# Hypnos_V0.net
KiCad netlist of a schematic drawn in EAGLE
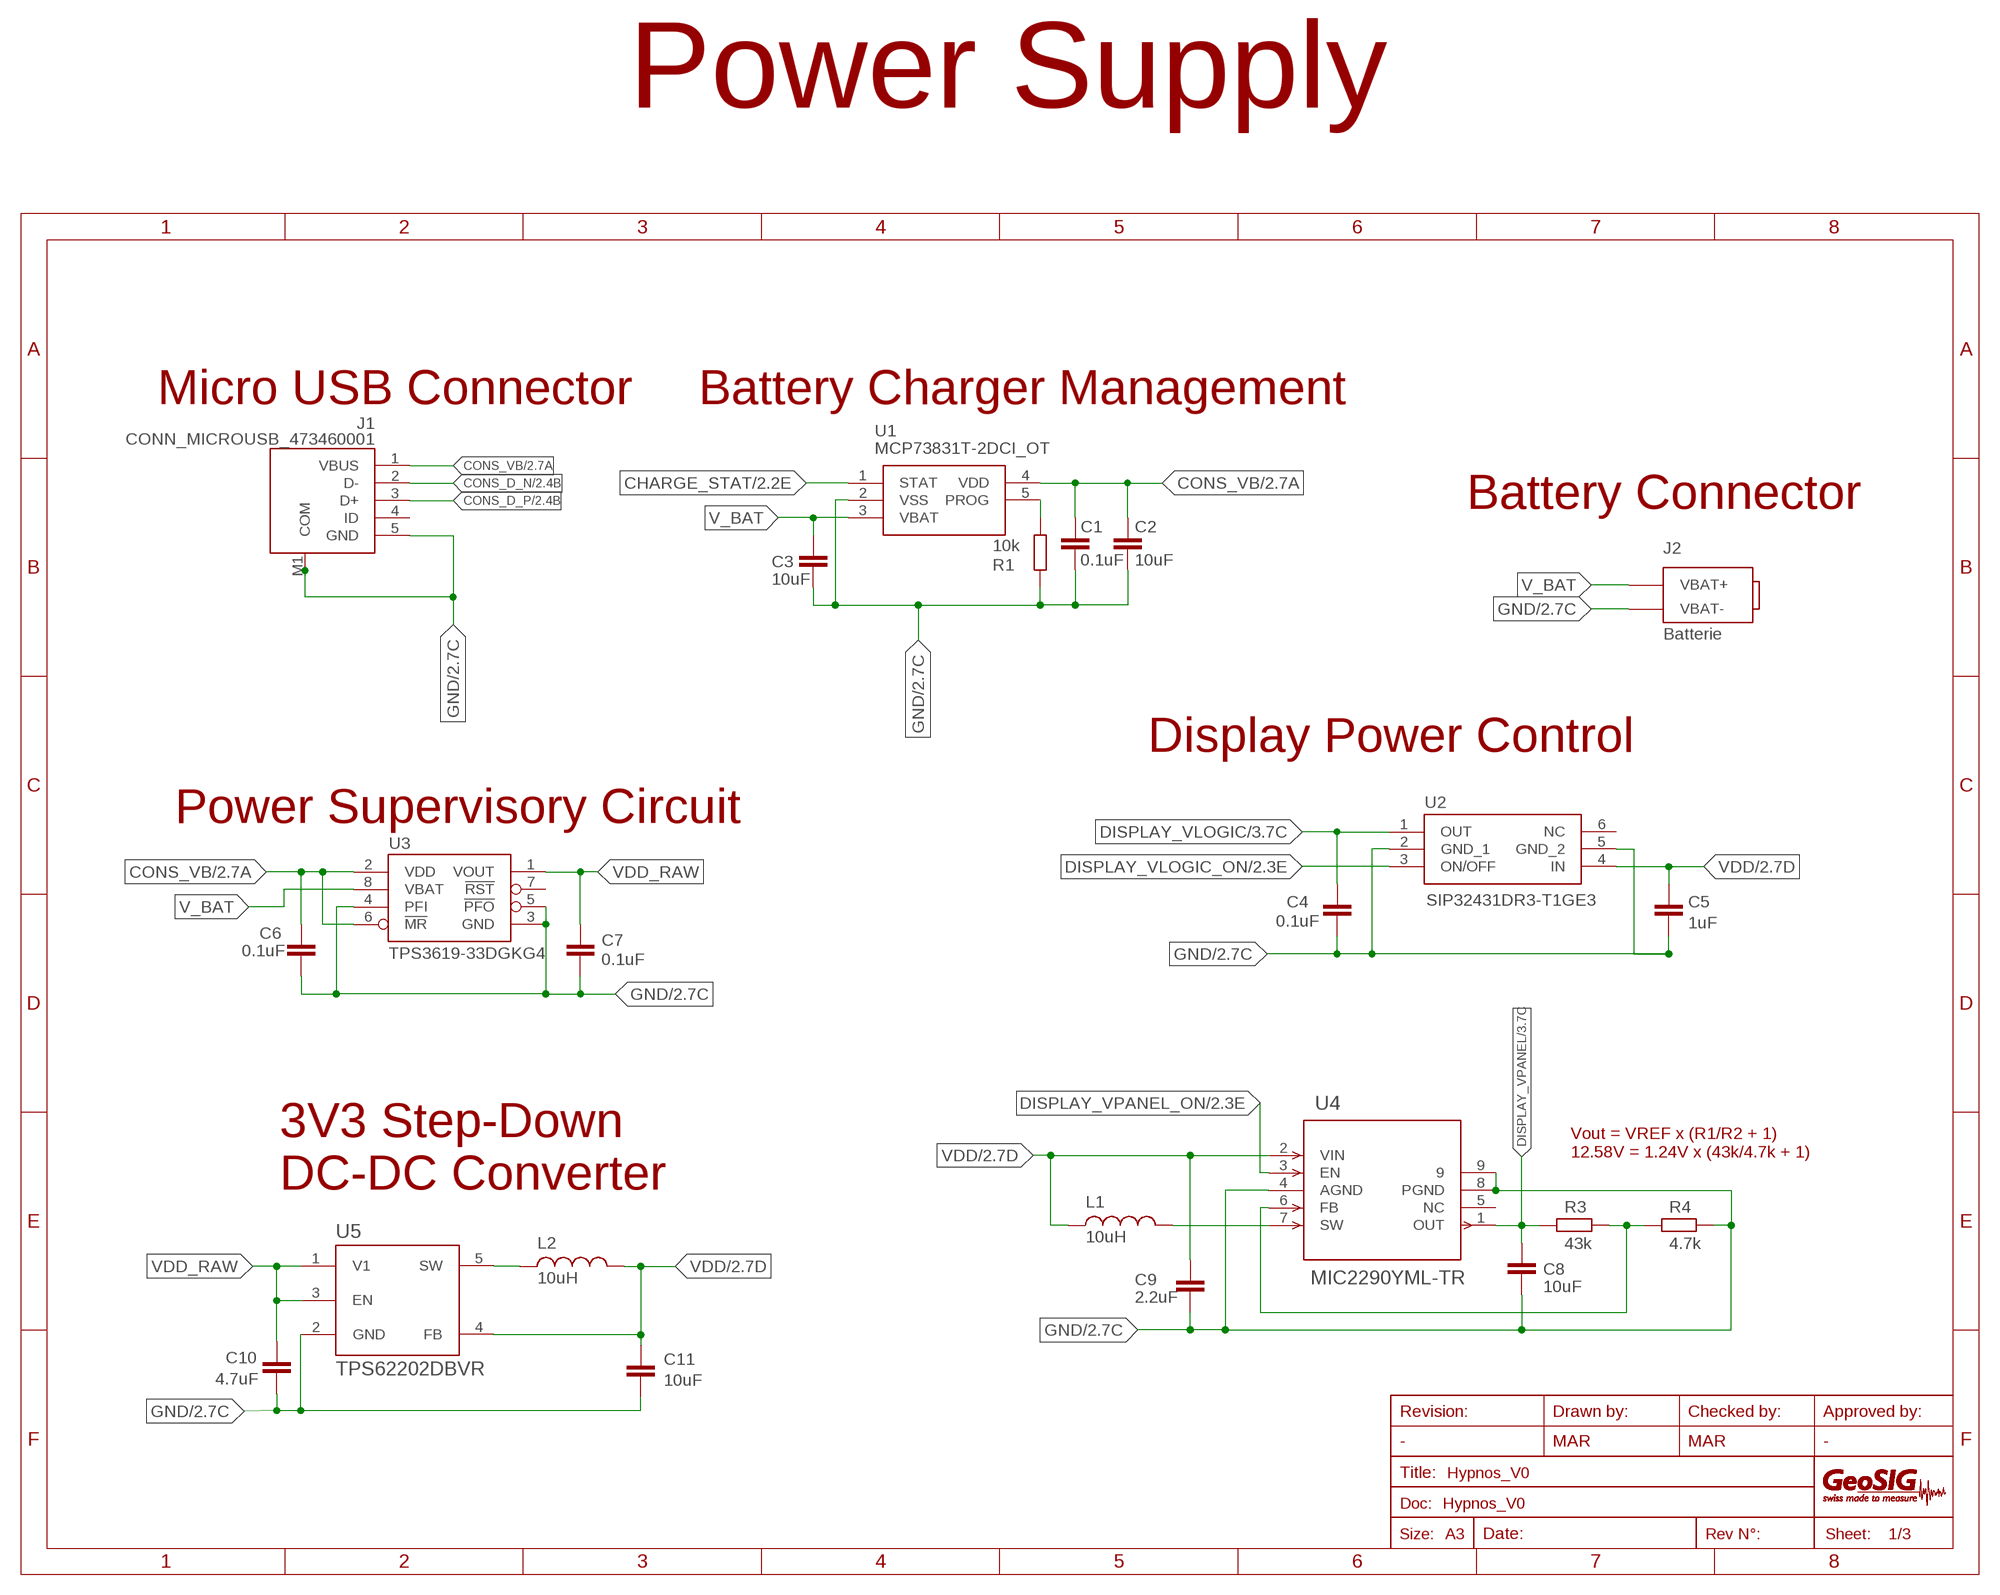
[diagram p0: schematic, sheet 1]
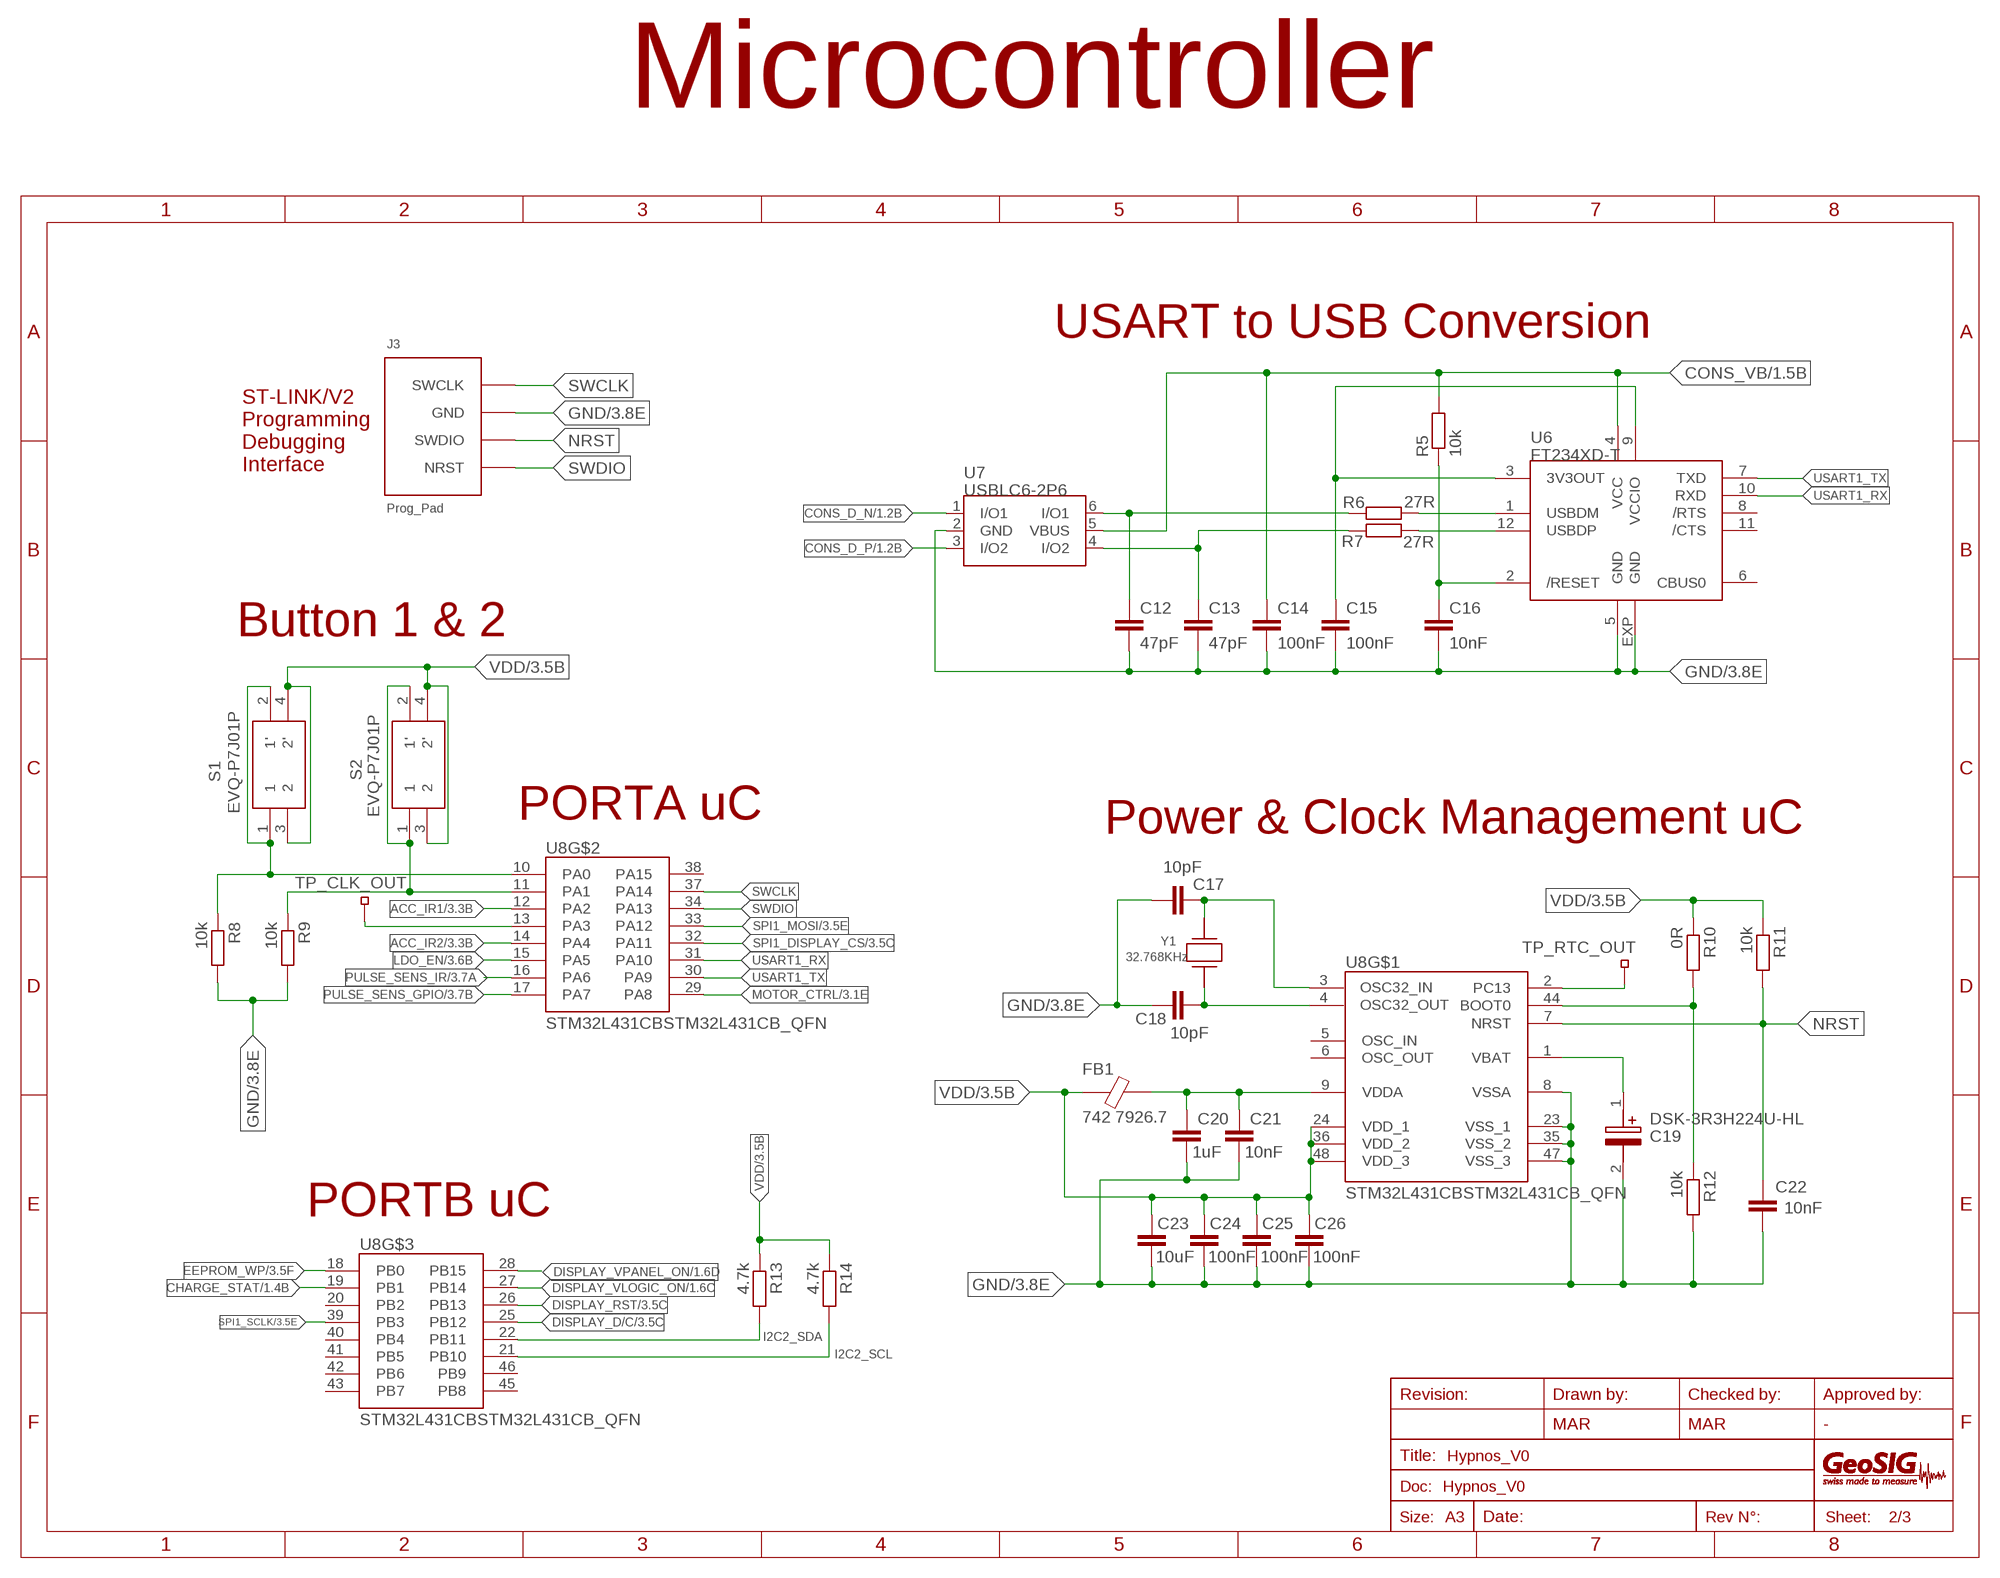
[diagram p1: schematic, sheet 2]
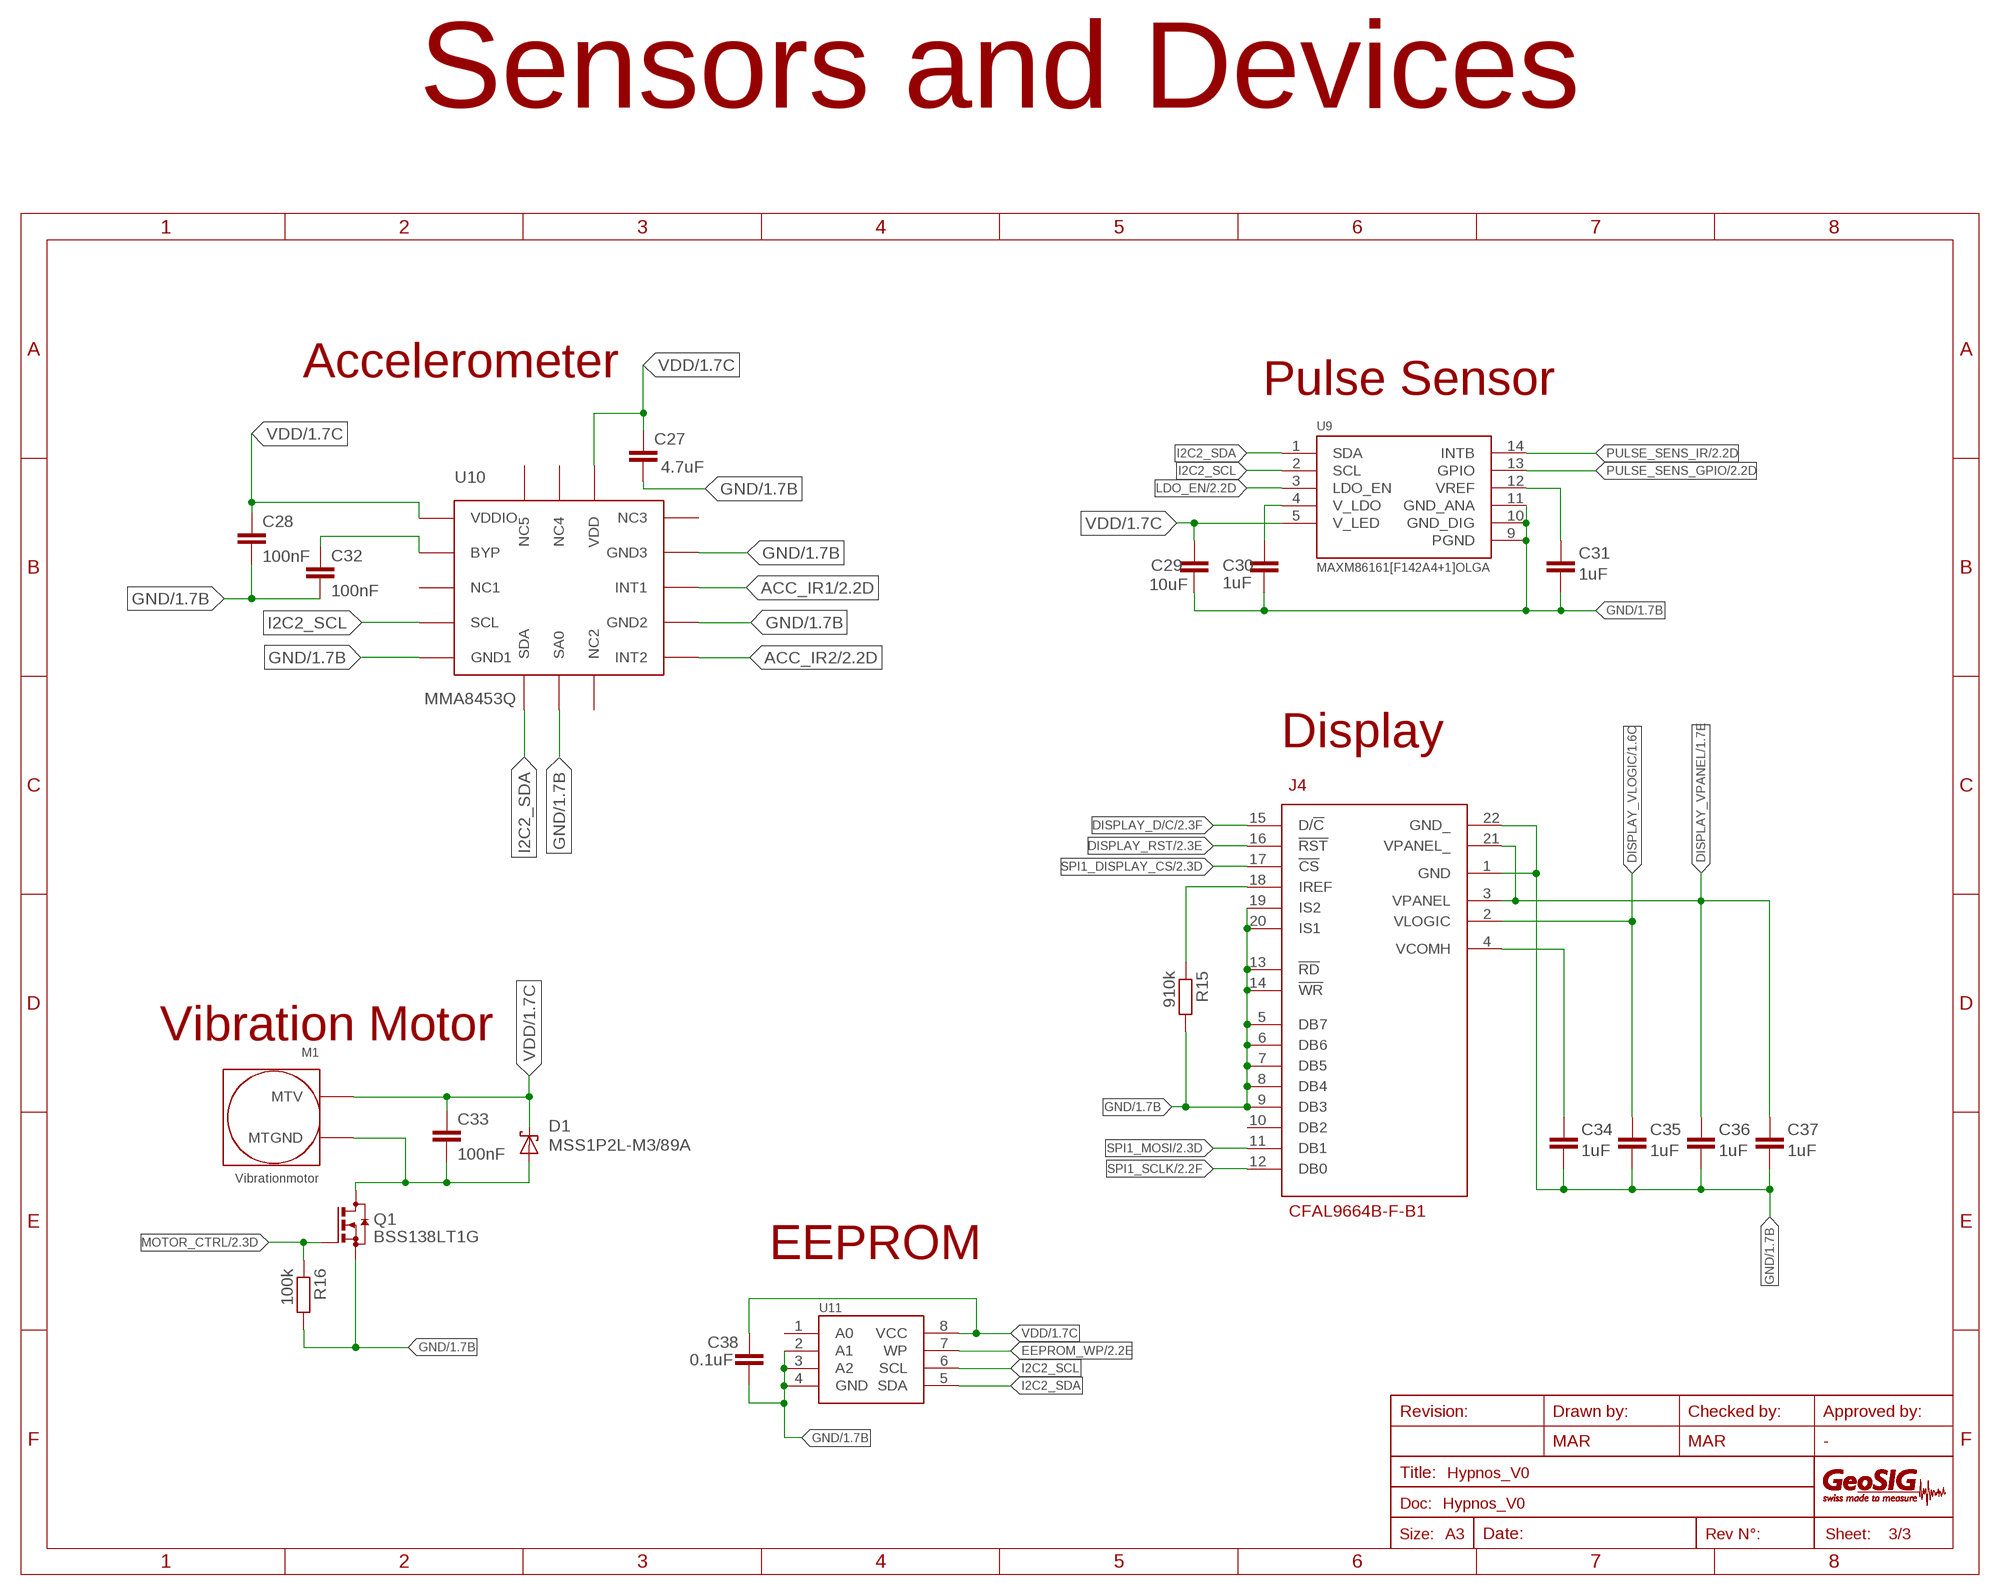
[diagram p2: schematic, sheet 3]

(export (version "E")
  (design (tool "Eeschema 10.0.6"))
  (components
    (comp (ref "C12")
      (value "47pF")
      (footprint "eagle-import:C0603K")
      (fields (field (name "MPN") "NONE"))
      (libsource (lib "eagle-import") (part "C0603"))
    )
    (comp (ref "C13")
      (value "47pF")
      (footprint "eagle-import:C0603K")
      (fields (field (name "MPN") "NONE"))
      (libsource (lib "eagle-import") (part "C0603"))
    )
    (comp (ref "C14")
      (value "100nF")
      (footprint "eagle-import:C0603K")
      (fields (field (name "MPN") "NONE"))
      (libsource (lib "eagle-import") (part "C0603"))
    )
    (comp (ref "C15")
      (value "100nF")
      (footprint "eagle-import:C0603K")
      (fields (field (name "MPN") "NONE"))
      (libsource (lib "eagle-import") (part "C0603"))
    )
    (comp (ref "C16")
      (value "10nF")
      (footprint "eagle-import:C0603K")
      (fields (field (name "MPN") "NONE"))
      (libsource (lib "eagle-import") (part "C0603"))
    )
    (comp (ref "C17")
      (value "10pF")
      (footprint "eagle-import:C0603K")
      (fields (field (name "MPN") "NONE"))
      (libsource (lib "eagle-import") (part "C0603"))
    )
    (comp (ref "C18")
      (value "10pF")
      (footprint "eagle-import:C0603K")
      (fields (field (name "MPN") "NONE"))
      (libsource (lib "eagle-import") (part "C0603"))
    )
    (comp (ref "C19")
      (value "DSK-3R3H224U-HL")
      (footprint "eagle-import:DSK3R3H334THL")
      (fields (field (name "MOUSER_PART_NUMBER") "555-DSK3R3H224U-HL"))
      (libsource (lib "eagle-import") (part "DSK-3R3H224U-HL"))
    )
    (comp (ref "C20")
      (value "1uF")
      (footprint "eagle-import:C0603K")
      (fields (field (name "MPN") "NONE"))
      (libsource (lib "eagle-import") (part "C0603"))
    )
    (comp (ref "C21")
      (value "10nF")
      (footprint "eagle-import:C0603K")
      (fields (field (name "MPN") "NONE"))
      (libsource (lib "eagle-import") (part "C0603"))
    )
    (comp (ref "C22")
      (value "10nF")
      (footprint "eagle-import:C0603K")
      (fields (field (name "MPN") "NONE"))
      (libsource (lib "eagle-import") (part "C0603"))
    )
    (comp (ref "C23")
      (value "10uF")
      (footprint "eagle-import:C0603K")
      (fields (field (name "MPN") "NONE"))
      (libsource (lib "eagle-import") (part "C0603"))
    )
    (comp (ref "C24")
      (value "100nF")
      (footprint "eagle-import:C0603K")
      (fields (field (name "MPN") "NONE"))
      (libsource (lib "eagle-import") (part "C0603"))
    )
    (comp (ref "C25")
      (value "100nF")
      (footprint "eagle-import:C0603K")
      (fields (field (name "MPN") "NONE"))
      (libsource (lib "eagle-import") (part "C0603"))
    )
    (comp (ref "C26")
      (value "100nF")
      (footprint "eagle-import:C0603K")
      (fields (field (name "MPN") "NONE"))
      (libsource (lib "eagle-import") (part "C0603"))
    )
    (comp (ref "FB1")
      (value "742 7926.7")
      (footprint "eagle-import:FB0603")
      (fields (field (name "MPN") "NONE"))
      (libsource (lib "eagle-import") (part "FERRITE_BEAD0603"))
    )
    (comp (ref "J3")
      (value "Prog_Pad")
      (footprint "eagle-import:PROG_PAD")
      (libsource (lib "eagle-import") (part "PROG_PAD"))
    )
    (comp (ref "R5")
      (value "10k")
      (footprint "eagle-import:R0603")
      (fields (field (name "MPN") "NONE"))
      (libsource (lib "eagle-import") (part "R-EU_R0603"))
    )
    (comp (ref "R6")
      (value "27R")
      (footprint "eagle-import:R0603")
      (fields (field (name "MPN") "NONE"))
      (libsource (lib "eagle-import") (part "R-EU_R0603"))
    )
    (comp (ref "R7")
      (value "27R")
      (footprint "eagle-import:R0603")
      (fields (field (name "MPN") "NONE"))
      (libsource (lib "eagle-import") (part "R-EU_R0603"))
    )
    (comp (ref "R8")
      (value "10k")
      (footprint "eagle-import:R0603")
      (fields (field (name "MPN") "NONE"))
      (libsource (lib "eagle-import") (part "R-EU_R0603"))
    )
    (comp (ref "R9")
      (value "10k")
      (footprint "eagle-import:R0603")
      (fields (field (name "MPN") "NONE"))
      (libsource (lib "eagle-import") (part "R-EU_R0603"))
    )
    (comp (ref "R10")
      (value "0R")
      (footprint "eagle-import:R0603")
      (fields (field (name "MPN") "NONE"))
      (libsource (lib "eagle-import") (part "R-EU_R0603"))
    )
    (comp (ref "R11")
      (value "10k")
      (footprint "eagle-import:R0603")
      (fields (field (name "MPN") "NONE"))
      (libsource (lib "eagle-import") (part "R-EU_R0603"))
    )
    (comp (ref "R12")
      (value "10k")
      (footprint "eagle-import:R0603")
      (fields (field (name "MPN") "NONE"))
      (libsource (lib "eagle-import") (part "R-EU_R0603"))
    )
    (comp (ref "R13")
      (value "4.7k")
      (footprint "eagle-import:R0603")
      (fields (field (name "MPN") "NONE"))
      (libsource (lib "eagle-import") (part "R-EU_R0603"))
    )
    (comp (ref "R14")
      (value "4.7k")
      (footprint "eagle-import:R0603")
      (fields (field (name "MPN") "NONE"))
      (libsource (lib "eagle-import") (part "R-EU_R0603"))
    )
    (comp (ref "S1")
      (value "EVQ-P7J01P")
      (footprint "eagle-import:EVQP7J01P")
      (fields (field (name "MOUSER_PART_NUMBER") "667-EVQP7J01P"))
      (libsource (lib "eagle-import") (part "EVQ-P7J01P"))
    )
    (comp (ref "S2")
      (value "EVQ-P7J01P")
      (footprint "eagle-import:EVQP7J01P")
      (fields (field (name "MOUSER_PART_NUMBER") "667-EVQP7J01P"))
      (libsource (lib "eagle-import") (part "EVQ-P7J01P"))
    )
    (comp (ref "TP_CLK_OUT")
      (value "TEST_PIN_SMD")
      (footprint "eagle-import:SMD_1")
      (fields (field (name "MPN") "NONE"))
      (libsource (lib "eagle-import") (part "TEST_PIN_SMD"))
    )
    (comp (ref "TP_RTC_OUT")
      (value "TEST_PIN_SMD")
      (footprint "eagle-import:SMD_1")
      (fields (field (name "MPN") "NONE"))
      (libsource (lib "eagle-import") (part "TEST_PIN_SMD"))
    )
    (comp (ref "U6")
      (value "FT234XD-T")
      (footprint "eagle-import:DFN12-3X3")
      (libsource (lib "eagle-import") (part "FT234XD-T"))
    )
    (comp (ref "U7")
      (value "USBLC6-2P6")
      (footprint "eagle-import:SOT666")
      (libsource (lib "eagle-import") (part "USBLC6-2P6"))
    )
    (comp (ref "U8")
      (value "STM32L431CBSTM32L431CB_QFN")
      (footprint "eagle-import:QFN50P700X700X60-49N")
      (libsource (lib "eagle-import") (part "STM32L431CBSTM32L431CB_QFN"))
    )
    (comp (ref "Y1")
      (value "32.768KHz")
      (footprint "eagle-import:CM315")
      (fields (field (name "MPN") "CM315-32.768KDZY-UT"))
      (libsource (lib "eagle-import") (part "QUARTZ1-CM315-32.768KDZY-UT"))
    )
    (comp (ref "C1")
      (value "0.1uF")
      (footprint "eagle-import:C0603K")
      (fields (field (name "MPN") "NONE"))
      (libsource (lib "eagle-import") (part "C0603"))
    )
    (comp (ref "C2")
      (value "10uF")
      (footprint "eagle-import:C0603K")
      (fields (field (name "MPN") "NONE"))
      (libsource (lib "eagle-import") (part "C0603"))
    )
    (comp (ref "C3")
      (value "10uF")
      (footprint "eagle-import:C0603K")
      (fields (field (name "MPN") "NONE"))
      (libsource (lib "eagle-import") (part "C0603"))
    )
    (comp (ref "C4")
      (value "0.1uF")
      (footprint "eagle-import:C0603K")
      (fields (field (name "MPN") "NONE"))
      (libsource (lib "eagle-import") (part "C0603"))
    )
    (comp (ref "C5")
      (value "1uF")
      (footprint "eagle-import:C0603K")
      (fields (field (name "MPN") "NONE"))
      (libsource (lib "eagle-import") (part "C0603"))
    )
    (comp (ref "C6")
      (value "0.1uF")
      (footprint "eagle-import:C0603K")
      (fields (field (name "MPN") "NONE"))
      (libsource (lib "eagle-import") (part "C0603"))
    )
    (comp (ref "C7")
      (value "0.1uF")
      (footprint "eagle-import:C0603K")
      (fields (field (name "MPN") "NONE"))
      (libsource (lib "eagle-import") (part "C0603"))
    )
    (comp (ref "C8")
      (value "10uF")
      (footprint "eagle-import:C0603K")
      (fields (field (name "MPN") "NONE"))
      (libsource (lib "eagle-import") (part "C0603"))
    )
    (comp (ref "C9")
      (value "2.2uF")
      (footprint "eagle-import:C0603K")
      (fields (field (name "MPN") "NONE"))
      (libsource (lib "eagle-import") (part "C0603"))
    )
    (comp (ref "C10")
      (value "4.7uF")
      (footprint "eagle-import:C0603K")
      (fields (field (name "MPN") "NONE"))
      (libsource (lib "eagle-import") (part "C0603"))
    )
    (comp (ref "C11")
      (value "10uF")
      (footprint "eagle-import:C0603K")
      (fields (field (name "MPN") "NONE"))
      (libsource (lib "eagle-import") (part "C0603"))
    )
    (comp (ref "J1")
      (value "CONN_MICROUSB_473460001")
      (footprint "eagle-import:CONN_MOLEX_473460001")
      (fields (field (name "MPN") "47346-0001"))
      (libsource (lib "eagle-import") (part "CONN_MICROUSB_473460001"))
    )
    (comp (ref "J2")
      (value "Batterie")
      (footprint "eagle-import:BATTERIE")
      (libsource (lib "eagle-import") (part "BATTERIE"))
    )
    (comp (ref "L1")
      (value "10uH")
      (footprint "eagle-import:L1210")
      (fields (field (name "MPN") "NONE"))
      (libsource (lib "eagle-import") (part "INDUCT1210"))
    )
    (comp (ref "L2")
      (value "10uH")
      (footprint "eagle-import:L1210")
      (fields (field (name "MPN") "NONE"))
      (libsource (lib "eagle-import") (part "INDUCT1210"))
    )
    (comp (ref "R1")
      (value "10k")
      (footprint "eagle-import:R0603")
      (fields (field (name "MPN") "NONE"))
      (libsource (lib "eagle-import") (part "R-EU_R0603"))
    )
    (comp (ref "R3")
      (value "43k")
      (footprint "eagle-import:R0603")
      (fields (field (name "MPN") "NONE"))
      (libsource (lib "eagle-import") (part "R-EU_R0603"))
    )
    (comp (ref "R4")
      (value "4.7k")
      (footprint "eagle-import:R0603")
      (fields (field (name "MPN") "NONE"))
      (libsource (lib "eagle-import") (part "R-EU_R0603"))
    )
    (comp (ref "U1")
      (value "MCP73831T-2DCI_OT")
      (footprint "eagle-import:SOT95P270X145-5N")
      (fields
        (field (name "MANUFACTURER_PART_NUMBER") "MCP73831T-2DCI/OT")
        (field (name "MOUSER_PART_NUMBER") "579-MCP73831T-2DCIOT")
      )
      (libsource (lib "eagle-import") (part "MCP73831T-2DCI_OT"))
    )
    (comp (ref "U2")
      (value "SIP32431DR3-T1GE3")
      (footprint "eagle-import:SOT65P210X110-6N")
      (fields (field (name "MOUSER_PART_NUMBER") "781-SIP32431DR3-GE3"))
      (libsource (lib "eagle-import") (part "SIP32431DR3-T1GE3"))
    )
    (comp (ref "U3")
      (value "TPS3619-33DGKG4")
      (footprint "eagle-import:MSOP8")
      (libsource (lib "eagle-import") (part "TPS3619-33DGKG4"))
    )
    (comp (ref "U4")
      (value "MIC2290YML-TR")
      (footprint "eagle-import:MLF-8_ML_MCH")
      (fields (field (name "COPYRIGHT") "Copyright (C) 2018 Accelerated Designs. All rights reserved"))
      (libsource (lib "eagle-import") (part "MIC2290YML-TR"))
    )
    (comp (ref "U5")
      (value "TPS62202DBVR")
      (footprint "eagle-import:SOT95P280X145-5N")
      (fields (field (name "MF") "Texas Instruments"))
      (libsource (lib "eagle-import") (part "TPS62202DBVR"))
    )
    (comp (ref "C27")
      (value "4.7uF")
      (footprint "eagle-import:C0603K")
      (fields (field (name "MPN") "NONE"))
      (libsource (lib "eagle-import") (part "C0603"))
    )
    (comp (ref "C28")
      (value "100nF")
      (footprint "eagle-import:C0603K")
      (fields (field (name "MPN") "NONE"))
      (libsource (lib "eagle-import") (part "C0603"))
    )
    (comp (ref "C29")
      (value "10uF")
      (footprint "eagle-import:C0603K")
      (fields (field (name "MPN") "NONE"))
      (libsource (lib "eagle-import") (part "C0603"))
    )
    (comp (ref "C30")
      (value "1uF")
      (footprint "eagle-import:C0603K")
      (fields (field (name "MPN") "NONE"))
      (libsource (lib "eagle-import") (part "C0603"))
    )
    (comp (ref "C31")
      (value "1uF")
      (footprint "eagle-import:C0603K")
      (fields (field (name "MPN") "NONE"))
      (libsource (lib "eagle-import") (part "C0603"))
    )
    (comp (ref "C32")
      (value "100nF")
      (footprint "eagle-import:C0603K")
      (fields (field (name "MPN") "NONE"))
      (libsource (lib "eagle-import") (part "C0603"))
    )
    (comp (ref "C33")
      (value "100nF")
      (footprint "eagle-import:C0603K")
      (fields (field (name "MPN") "NONE"))
      (libsource (lib "eagle-import") (part "C0603"))
    )
    (comp (ref "C34")
      (value "1uF")
      (footprint "eagle-import:C0603K")
      (fields (field (name "MPN") "NONE"))
      (libsource (lib "eagle-import") (part "C0603"))
    )
    (comp (ref "C35")
      (value "1uF")
      (footprint "eagle-import:C0603K")
      (fields (field (name "MPN") "NONE"))
      (libsource (lib "eagle-import") (part "C0603"))
    )
    (comp (ref "C36")
      (value "1uF")
      (footprint "eagle-import:C0603K")
      (fields (field (name "MPN") "NONE"))
      (libsource (lib "eagle-import") (part "C0603"))
    )
    (comp (ref "C37")
      (value "1uF")
      (footprint "eagle-import:C0603K")
      (fields (field (name "MPN") "NONE"))
      (libsource (lib "eagle-import") (part "C0603"))
    )
    (comp (ref "C38")
      (value "0.1uF")
      (footprint "eagle-import:C0603K")
      (fields (field (name "MPN") "NONE"))
      (libsource (lib "eagle-import") (part "C0603"))
    )
    (comp (ref "D1")
      (value "MSS1P2L-M3/89A")
      (footprint "eagle-import:MICROSMP")
      (libsource (lib "eagle-import") (part "MSS1P2L-M3/89A"))
    )
    (comp (ref "J4")
      (value "CFAL9664B-F-B1")
      (footprint "eagle-import:CFAL9664B-F-B1")
      (libsource (lib "eagle-import") (part "CFAL9664B-F-B1"))
    )
    (comp (ref "M1")
      (value "Vibrationmotor")
      (footprint "eagle-import:VIBRATIONMOTOR")
      (libsource (lib "eagle-import") (part "VIBRATIONMOTOR"))
    )
    (comp (ref "Q1")
      (value "BSS138LT1G")
      (footprint "eagle-import:SOT23")
      (libsource (lib "eagle-import") (part "BSS138LT1G"))
    )
    (comp (ref "R15")
      (value "910k")
      (footprint "eagle-import:R0603")
      (fields (field (name "MPN") "NONE"))
      (libsource (lib "eagle-import") (part "R-EU_R0603"))
    )
    (comp (ref "R16")
      (value "100k")
      (footprint "eagle-import:R0603")
      (fields (field (name "MPN") "NONE"))
      (libsource (lib "eagle-import") (part "R-EU_R0603"))
    )
    (comp (ref "U9")
      (value "MAXM86161[F142A4+1]OLGA")
      (footprint "eagle-import:MAXM86161")
      (libsource (lib "eagle-import") (part "MAXM86161[F142A4+1]OLGA"))
    )
    (comp (ref "U10")
      (value "MMA8453Q")
      (footprint "eagle-import:QFN-COL")
      (fields (field (name "MF") "NXP Semiconductors"))
      (libsource (lib "eagle-import") (part "MMA8453Q"))
    )
    (comp (ref "U11")
      (value "BR24T1MFJ-3AME2")
      (footprint "eagle-import:SOIC127P600X165-8N")
      (libsource (lib "eagle-import") (part "BR24T1MFJ-3AME2"))
    )
  )
  (nets
    (net (code "1") (name "ACC_IR1") (class "Default")
      (node (ref "U10") (pin "P$11") (pinfunction "INT1_P$11") (pintype "bidirectional"))
      (node (ref "U8") (pin "12") (pinfunction "PA2_12") (pintype "bidirectional"))
    )
    (net (code "2") (name "ACC_IR2") (class "Default")
      (node (ref "U10") (pin "P$9") (pinfunction "INT2_P$9") (pintype "bidirectional"))
      (node (ref "U8") (pin "14") (pinfunction "PA4_14") (pintype "bidirectional"))
    )
    (net (code "3") (name "CHARGE_STAT") (class "Default")
      (node (ref "U1") (pin "1") (pinfunction "STAT_1") (pintype "bidirectional"))
      (node (ref "U8") (pin "19") (pinfunction "PB1_19") (pintype "bidirectional"))
    )
    (net (code "4") (name "CONS_D_N") (class "Default")
      (node (ref "J1") (pin "2") (pinfunction "D-_2") (pintype "bidirectional"))
      (node (ref "U7") (pin "1") (pinfunction "I/O1_1") (pintype "bidirectional"))
    )
    (net (code "5") (name "CONS_D_P") (class "Default")
      (node (ref "J1") (pin "3") (pinfunction "D+_3") (pintype "bidirectional"))
      (node (ref "U7") (pin "3") (pinfunction "I/O2_3") (pintype "bidirectional"))
    )
    (net (code "6") (name "CONS_VB") (class "Default")
      (node (ref "C1") (pin "1") (pinfunction "1_1") (pintype "passive"))
      (node (ref "C14") (pin "1") (pinfunction "1_1") (pintype "passive"))
      (node (ref "C2") (pin "1") (pinfunction "1_1") (pintype "passive"))
      (node (ref "C6") (pin "1") (pinfunction "1_1") (pintype "passive"))
      (node (ref "J1") (pin "1") (pinfunction "VBUS_1") (pintype "power_in"))
      (node (ref "R5") (pin "2") (pinfunction "2_2") (pintype "passive"))
      (node (ref "U1") (pin "4") (pinfunction "VDD_4") (pintype "bidirectional"))
      (node (ref "U3") (pin "2") (pinfunction "VDD_2") (pintype "power_in"))
      (node (ref "U3") (pin "6") (pinfunction "~{MR}_6") (pintype "passive"))
      (node (ref "U6") (pin "4") (pinfunction "VCC_4") (pintype "power_in"))
      (node (ref "U7") (pin "5") (pinfunction "VBUS_5") (pintype "input"))
    )
    (net (code "7") (name "DISPLAY_D{slash}C") (class "Default")
      (node (ref "J4") (pin "15") (pinfunction "D/~{C}_15") (pintype "input"))
      (node (ref "U8") (pin "25") (pinfunction "PB12_25") (pintype "bidirectional"))
    )
    (net (code "8") (name "DISPLAY_RST") (class "Default")
      (node (ref "J4") (pin "16") (pinfunction "~{RST}_16") (pintype "input"))
      (node (ref "U8") (pin "26") (pinfunction "PB13_26") (pintype "bidirectional"))
    )
    (net (code "9") (name "DISPLAY_VLOGIC") (class "Default")
      (node (ref "C35") (pin "1") (pinfunction "1_1") (pintype "passive"))
      (node (ref "C4") (pin "1") (pinfunction "1_1") (pintype "passive"))
      (node (ref "J4") (pin "2") (pinfunction "VLOGIC_2") (pintype "power_in"))
      (node (ref "U2") (pin "1") (pinfunction "OUT_1") (pintype "bidirectional"))
    )
    (net (code "10") (name "DISPLAY_VLOGIC_ON") (class "Default")
      (node (ref "U2") (pin "3") (pinfunction "ON/OFF_3") (pintype "bidirectional"))
      (node (ref "U8") (pin "27") (pinfunction "PB14_27") (pintype "bidirectional"))
    )
    (net (code "11") (name "DISPLAY_VPANEL") (class "Default")
      (node (ref "C36") (pin "1") (pinfunction "1_1") (pintype "passive"))
      (node (ref "C37") (pin "1") (pinfunction "1_1") (pintype "passive"))
      (node (ref "C8") (pin "1") (pinfunction "1_1") (pintype "passive"))
      (node (ref "J4") (pin "21") (pinfunction "VPANEL__21") (pintype "power_in"))
      (node (ref "J4") (pin "3") (pinfunction "VPANEL_3") (pintype "power_in"))
      (node (ref "R3") (pin "2") (pinfunction "2_2") (pintype "passive"))
      (node (ref "U4") (pin "1") (pinfunction "OUT_1") (pintype "output"))
    )
    (net (code "12") (name "DISPLAY_VPANEL_ON") (class "Default")
      (node (ref "U4") (pin "3") (pinfunction "EN_3") (pintype "input"))
      (node (ref "U8") (pin "28") (pinfunction "PB15_28") (pintype "bidirectional"))
    )
    (net (code "13") (name "EEPROM_WP") (class "Default")
      (node (ref "U11") (pin "7") (pinfunction "WP_7") (pintype "input"))
      (node (ref "U8") (pin "18") (pinfunction "PB0_18") (pintype "bidirectional"))
    )
    (net (code "14") (name "GND") (class "Default")
      (node (ref "C1") (pin "2") (pinfunction "2_2") (pintype "passive"))
      (node (ref "C10") (pin "2") (pinfunction "2_2") (pintype "passive"))
      (node (ref "C11") (pin "2") (pinfunction "2_2") (pintype "passive"))
      (node (ref "C12") (pin "2") (pinfunction "2_2") (pintype "passive"))
      (node (ref "C13") (pin "2") (pinfunction "2_2") (pintype "passive"))
      (node (ref "C14") (pin "2") (pinfunction "2_2") (pintype "passive"))
      (node (ref "C15") (pin "2") (pinfunction "2_2") (pintype "passive"))
      (node (ref "C16") (pin "2") (pinfunction "2_2") (pintype "passive"))
      (node (ref "C17") (pin "2") (pinfunction "2_2") (pintype "passive"))
      (node (ref "C18") (pin "2") (pinfunction "2_2") (pintype "passive"))
      (node (ref "C19") (pin "2") (pinfunction "-_2") (pintype "bidirectional"))
      (node (ref "C2") (pin "2") (pinfunction "2_2") (pintype "passive"))
      (node (ref "C20") (pin "2") (pinfunction "2_2") (pintype "passive"))
      (node (ref "C21") (pin "2") (pinfunction "2_2") (pintype "passive"))
      (node (ref "C22") (pin "2") (pinfunction "2_2") (pintype "passive"))
      (node (ref "C23") (pin "2") (pinfunction "2_2") (pintype "passive"))
      (node (ref "C24") (pin "2") (pinfunction "2_2") (pintype "passive"))
      (node (ref "C25") (pin "2") (pinfunction "2_2") (pintype "passive"))
      (node (ref "C26") (pin "2") (pinfunction "2_2") (pintype "passive"))
      (node (ref "C27") (pin "2") (pinfunction "2_2") (pintype "passive"))
      (node (ref "C28") (pin "2") (pinfunction "2_2") (pintype "passive"))
      (node (ref "C29") (pin "2") (pinfunction "2_2") (pintype "passive"))
      (node (ref "C3") (pin "2") (pinfunction "2_2") (pintype "passive"))
      (node (ref "C30") (pin "2") (pinfunction "2_2") (pintype "passive"))
      (node (ref "C31") (pin "2") (pinfunction "2_2") (pintype "passive"))
      (node (ref "C32") (pin "2") (pinfunction "2_2") (pintype "passive"))
      (node (ref "C34") (pin "2") (pinfunction "2_2") (pintype "passive"))
      (node (ref "C35") (pin "2") (pinfunction "2_2") (pintype "passive"))
      (node (ref "C36") (pin "2") (pinfunction "2_2") (pintype "passive"))
      (node (ref "C37") (pin "2") (pinfunction "2_2") (pintype "passive"))
      (node (ref "C38") (pin "2") (pinfunction "2_2") (pintype "passive"))
      (node (ref "C4") (pin "2") (pinfunction "2_2") (pintype "passive"))
      (node (ref "C5") (pin "2") (pinfunction "2_2") (pintype "passive"))
      (node (ref "C6") (pin "2") (pinfunction "2_2") (pintype "passive"))
      (node (ref "C7") (pin "2") (pinfunction "2_2") (pintype "passive"))
      (node (ref "C8") (pin "2") (pinfunction "2_2") (pintype "passive"))
      (node (ref "C9") (pin "2") (pinfunction "2_2") (pintype "passive"))
      (node (ref "J1") (pin "5") (pinfunction "GND_5") (pintype "power_in"))
      (node (ref "J1") (pin "M1") (pinfunction "COM_M1") (pintype "passive"))
      (node (ref "J1") (pin "M2") (pinfunction "COM_M2") (pintype "passive"))
      (node (ref "J1") (pin "M3") (pinfunction "COM_M3") (pintype "passive"))
      (node (ref "J1") (pin "M4") (pinfunction "COM_M4") (pintype "passive"))
      (node (ref "J1") (pin "M5") (pinfunction "COM_M5") (pintype "passive"))
      (node (ref "J1") (pin "M6") (pinfunction "COM_M6") (pintype "passive"))
      (node (ref "J2") (pin "2") (pinfunction "VBAT-_2") (pintype "power_in"))
      (node (ref "J3") (pin "2") (pinfunction "GND_2") (pintype "bidirectional"))
      (node (ref "J4") (pin "1") (pinfunction "GND_1") (pintype "power_in"))
      (node (ref "J4") (pin "13") (pinfunction "~{RD}_13") (pintype "input"))
      (node (ref "J4") (pin "14") (pinfunction "~{WR}_14") (pintype "input"))
      (node (ref "J4") (pin "19") (pinfunction "IS2_19") (pintype "input"))
      (node (ref "J4") (pin "20") (pinfunction "IS1_20") (pintype "input"))
      (node (ref "J4") (pin "22") (pinfunction "GND__22") (pintype "power_in"))
      (node (ref "J4") (pin "5") (pinfunction "DB7_5") (pintype "bidirectional"))
      (node (ref "J4") (pin "6") (pinfunction "DB6_6") (pintype "bidirectional"))
      (node (ref "J4") (pin "7") (pinfunction "DB5_7") (pintype "bidirectional"))
      (node (ref "J4") (pin "8") (pinfunction "DB4_8") (pintype "bidirectional"))
      (node (ref "J4") (pin "9") (pinfunction "DB3_9") (pintype "bidirectional"))
      (node (ref "Q1") (pin "2") (pinfunction "S_2") (pintype "passive"))
      (node (ref "R1") (pin "2") (pinfunction "2_2") (pintype "passive"))
      (node (ref "R12") (pin "2") (pinfunction "2_2") (pintype "passive"))
      (node (ref "R15") (pin "2") (pinfunction "2_2") (pintype "passive"))
      (node (ref "R16") (pin "2") (pinfunction "2_2") (pintype "passive"))
      (node (ref "R4") (pin "1") (pinfunction "1_1") (pintype "passive"))
      (node (ref "R8") (pin "2") (pinfunction "2_2") (pintype "passive"))
      (node (ref "R9") (pin "2") (pinfunction "2_2") (pintype "passive"))
      (node (ref "U1") (pin "2") (pinfunction "VSS_2") (pintype "bidirectional"))
      (node (ref "U10") (pin "P$10") (pinfunction "GND2_P$10") (pintype "bidirectional"))
      (node (ref "U10") (pin "P$12") (pinfunction "GND3_P$12") (pintype "bidirectional"))
      (node (ref "U10") (pin "P$5") (pinfunction "GND1_P$5") (pintype "bidirectional"))
      (node (ref "U10") (pin "P$7") (pinfunction "SA0_P$7") (pintype "bidirectional"))
      (node (ref "U11") (pin "2") (pinfunction "A1_2") (pintype "input"))
      (node (ref "U11") (pin "3") (pinfunction "A2_3") (pintype "input"))
      (node (ref "U11") (pin "4") (pinfunction "GND_4") (pintype "power_in"))
      (node (ref "U2") (pin "2") (pinfunction "GND_1_2") (pintype "bidirectional"))
      (node (ref "U2") (pin "5") (pinfunction "GND_2_5") (pintype "bidirectional"))
      (node (ref "U3") (pin "3") (pinfunction "GND_3") (pintype "power_in"))
      (node (ref "U3") (pin "4") (pinfunction "PFI_4") (pintype "power_in"))
      (node (ref "U3") (pin "5") (pinfunction "~{PFO}_5") (pintype "passive"))
      (node (ref "U4") (pin "4") (pinfunction "AGND_4") (pintype "power_in"))
      (node (ref "U4") (pin "8") (pinfunction "PGND_8") (pintype "power_in"))
      (node (ref "U4") (pin "9") (pinfunction "9_9") (pintype "passive"))
      (node (ref "U5") (pin "2") (pinfunction "GND_2") (pintype "passive"))
      (node (ref "U6") (pin "5") (pinfunction "GND_5") (pintype "power_in"))
      (node (ref "U6") (pin "EXP") (pinfunction "GND_EXP") (pintype "power_in"))
      (node (ref "U7") (pin "2") (pinfunction "GND_2") (pintype "input"))
      (node (ref "U8") (pin "23") (pinfunction "VSS_1_23") (pintype "power_in"))
      (node (ref "U8") (pin "35") (pinfunction "VSS_2_35") (pintype "power_in"))
      (node (ref "U8") (pin "47") (pinfunction "VSS_3_47") (pintype "power_in"))
      (node (ref "U8") (pin "8") (pinfunction "VSSA_8") (pintype "power_in"))
      (node (ref "U9") (pin "10") (pinfunction "GND_DIG_10") (pintype "power_in"))
      (node (ref "U9") (pin "11") (pinfunction "GND_ANA_11") (pintype "power_in"))
      (node (ref "U9") (pin "9") (pinfunction "PGND_9") (pintype "power_in"))
    )
    (net (code "15") (name "I2C2_SCL") (class "Default")
      (node (ref "R14") (pin "2") (pinfunction "2_2") (pintype "passive"))
      (node (ref "U10") (pin "P$4") (pinfunction "SCL_P$4") (pintype "bidirectional"))
      (node (ref "U11") (pin "6") (pinfunction "SCL_6") (pintype "bidirectional"))
      (node (ref "U8") (pin "21") (pinfunction "PB10_21") (pintype "bidirectional"))
      (node (ref "U9") (pin "2") (pinfunction "SCL_2") (pintype "bidirectional"))
    )
    (net (code "16") (name "I2C2_SDA") (class "Default")
      (node (ref "R13") (pin "2") (pinfunction "2_2") (pintype "passive"))
      (node (ref "U10") (pin "P$6") (pinfunction "SDA_P$6") (pintype "bidirectional"))
      (node (ref "U11") (pin "5") (pinfunction "SDA_5") (pintype "bidirectional"))
      (node (ref "U8") (pin "22") (pinfunction "PB11_22") (pintype "bidirectional"))
      (node (ref "U9") (pin "1") (pinfunction "SDA_1") (pintype "bidirectional"))
    )
    (net (code "17") (name "LDO_EN") (class "Default")
      (node (ref "U8") (pin "15") (pinfunction "PA5_15") (pintype "bidirectional"))
      (node (ref "U9") (pin "3") (pinfunction "LDO_EN_3") (pintype "input"))
    )
    (net (code "18") (name "MOTOR_CTRL") (class "Default")
      (node (ref "Q1") (pin "1") (pinfunction "G_1") (pintype "passive"))
      (node (ref "R16") (pin "1") (pinfunction "1_1") (pintype "passive"))
      (node (ref "U8") (pin "29") (pinfunction "PA8_29") (pintype "bidirectional"))
    )
    (net (code "19") (name "NRST") (class "Default")
      (node (ref "C22") (pin "1") (pinfunction "1_1") (pintype "passive"))
      (node (ref "J3") (pin "3") (pinfunction "SWDIO_3") (pintype "bidirectional"))
      (node (ref "R11") (pin "2") (pinfunction "2_2") (pintype "passive"))
      (node (ref "U8") (pin "7") (pinfunction "NRST_7") (pintype "bidirectional"))
    )
    (net (code "20") (name "Net-(C12-Pad1)") (class "Default")
      (node (ref "C12") (pin "1") (pinfunction "1_1") (pintype "passive"))
      (node (ref "R6") (pin "2") (pinfunction "2_2") (pintype "passive"))
      (node (ref "U7") (pin "6") (pinfunction "I/O1_6") (pintype "bidirectional"))
    )
    (net (code "21") (name "Net-(C13-Pad1)") (class "Default")
      (node (ref "C13") (pin "1") (pinfunction "1_1") (pintype "passive"))
      (node (ref "R7") (pin "2") (pinfunction "2_2") (pintype "passive"))
      (node (ref "U7") (pin "4") (pinfunction "I/O2_4") (pintype "bidirectional"))
    )
    (net (code "22") (name "Net-(C19-+)") (class "Default")
      (node (ref "C19") (pin "1") (pinfunction "+_1") (pintype "bidirectional"))
      (node (ref "U8") (pin "1") (pinfunction "VBAT_1") (pintype "bidirectional"))
    )
    (net (code "23") (name "Net-(FB1-P$2)") (class "Default")
      (node (ref "C20") (pin "1") (pinfunction "1_1") (pintype "passive"))
      (node (ref "C21") (pin "1") (pinfunction "1_1") (pintype "passive"))
      (node (ref "FB1") (pin "2") (pinfunction "P$2_2") (pintype "passive"))
      (node (ref "U8") (pin "9") (pinfunction "VDDA_9") (pintype "power_in"))
    )
    (net (code "24") (name "Net-(J4-IREF)") (class "Default")
      (node (ref "J4") (pin "18") (pinfunction "IREF_18") (pintype "output"))
      (node (ref "R15") (pin "1") (pinfunction "1_1") (pintype "passive"))
    )
    (net (code "25") (name "Net-(J4-VCOMH)") (class "Default")
      (node (ref "C34") (pin "1") (pinfunction "1_1") (pintype "passive"))
      (node (ref "J4") (pin "4") (pinfunction "VCOMH_4") (pintype "output"))
    )
    (net (code "26") (name "Net-(L1-P$2)") (class "Default")
      (node (ref "L1") (pin "2") (pinfunction "P$2_2") (pintype "passive"))
      (node (ref "U4") (pin "7") (pinfunction "SW_7") (pintype "input"))
    )
    (net (code "27") (name "Net-(L2-P$1)") (class "Default")
      (node (ref "L2") (pin "1") (pinfunction "P$1_1") (pintype "passive"))
      (node (ref "U5") (pin "5") (pinfunction "SW_5") (pintype "output"))
    )
    (net (code "28") (name "Net-(M1-MTGND)") (class "Default")
      (node (ref "C33") (pin "2") (pinfunction "2_2") (pintype "passive"))
      (node (ref "D1") (pin "A") (pinfunction "A_A") (pintype "passive"))
      (node (ref "M1") (pin "1") (pinfunction "MTGND_1") (pintype "bidirectional"))
      (node (ref "Q1") (pin "3") (pinfunction "D_3") (pintype "passive"))
    )
    (net (code "29") (name "Net-(S1-1')") (class "Default")
      (node (ref "R8") (pin "1") (pinfunction "1_1") (pintype "passive"))
      (node (ref "S1") (pin "1") (pinfunction "1_1") (pintype "bidirectional"))
      (node (ref "S1") (pin "2") (pinfunction "1'_2") (pintype "bidirectional"))
      (node (ref "U8") (pin "10") (pinfunction "PA0_10") (pintype "bidirectional"))
    )
    (net (code "30") (name "Net-(S2-1')") (class "Default")
      (node (ref "R9") (pin "1") (pinfunction "1_1") (pintype "passive"))
      (node (ref "S2") (pin "1") (pinfunction "1_1") (pintype "bidirectional"))
      (node (ref "S2") (pin "2") (pinfunction "1'_2") (pintype "bidirectional"))
      (node (ref "U8") (pin "11") (pinfunction "PA1_11") (pintype "bidirectional"))
    )
    (net (code "31") (name "Net-(TP_CLK_OUT-1)") (class "Default")
      (node (ref "TP_CLK_OUT") (pin "P$1") (pinfunction "1_P$1") (pintype "passive"))
      (node (ref "U8") (pin "13") (pinfunction "PA3_13") (pintype "bidirectional"))
    )
    (net (code "32") (name "Net-(TP_RTC_OUT-1)") (class "Default")
      (node (ref "TP_RTC_OUT") (pin "P$1") (pinfunction "1_P$1") (pintype "passive"))
      (node (ref "U8") (pin "2") (pinfunction "PC13_2") (pintype "bidirectional"))
    )
    (net (code "33") (name "Net-(U1-PROG)") (class "Default")
      (node (ref "R1") (pin "1") (pinfunction "1_1") (pintype "passive"))
      (node (ref "U1") (pin "5") (pinfunction "PROG_5") (pintype "bidirectional"))
    )
    (net (code "34") (name "Net-(U4-FB)") (class "Default")
      (node (ref "R3") (pin "1") (pinfunction "1_1") (pintype "passive"))
      (node (ref "R4") (pin "2") (pinfunction "2_2") (pintype "passive"))
      (node (ref "U4") (pin "6") (pinfunction "FB_6") (pintype "input"))
    )
    (net (code "35") (name "Net-(U6-3V3OUT)") (class "Default")
      (node (ref "C15") (pin "1") (pinfunction "1_1") (pintype "passive"))
      (node (ref "U6") (pin "3") (pinfunction "3V3OUT_3") (pintype "output"))
      (node (ref "U6") (pin "9") (pinfunction "VCCIO_9") (pintype "power_in"))
    )
    (net (code "36") (name "Net-(U6-USBDM)") (class "Default")
      (node (ref "R6") (pin "1") (pinfunction "1_1") (pintype "passive"))
      (node (ref "U6") (pin "1") (pinfunction "USBDM_1") (pintype "bidirectional"))
    )
    (net (code "37") (name "Net-(U6-USBDP)") (class "Default")
      (node (ref "R7") (pin "1") (pinfunction "1_1") (pintype "passive"))
      (node (ref "U6") (pin "12") (pinfunction "USBDP_12") (pintype "bidirectional"))
    )
    (net (code "38") (name "Net-(U6-{slash}RESET)") (class "Default")
      (node (ref "C16") (pin "1") (pinfunction "1_1") (pintype "passive"))
      (node (ref "R5") (pin "1") (pinfunction "1_1") (pintype "passive"))
      (node (ref "U6") (pin "2") (pinfunction "/RESET_2") (pintype "input"))
    )
    (net (code "39") (name "Net-(U8A-BOOT0)") (class "Default")
      (node (ref "R10") (pin "2") (pinfunction "2_2") (pintype "passive"))
      (node (ref "R12") (pin "1") (pinfunction "1_1") (pintype "passive"))
      (node (ref "U8") (pin "44") (pinfunction "BOOT0_44") (pintype "bidirectional"))
    )
    (net (code "40") (name "Net-(U8A-OSC32_IN)") (class "Default")
      (node (ref "C17") (pin "1") (pinfunction "1_1") (pintype "passive"))
      (node (ref "U8") (pin "3") (pinfunction "OSC32_IN_3") (pintype "bidirectional"))
      (node (ref "Y1") (pin "P$1") (pinfunction "P$1_P$1") (pintype "passive"))
    )
    (net (code "41") (name "Net-(U8A-OSC32_OUT)") (class "Default")
      (node (ref "C18") (pin "1") (pinfunction "1_1") (pintype "passive"))
      (node (ref "U8") (pin "4") (pinfunction "OSC32_OUT_4") (pintype "bidirectional"))
      (node (ref "Y1") (pin "P$2") (pinfunction "P$2_P$2") (pintype "passive"))
    )
    (net (code "42") (name "Net-(U9-VREF)") (class "Default")
      (node (ref "C31") (pin "1") (pinfunction "1_1") (pintype "passive"))
      (node (ref "U9") (pin "12") (pinfunction "VREF_12") (pintype "power_in"))
    )
    (net (code "43") (name "Net-(U9-V_LDO)") (class "Default")
      (node (ref "C30") (pin "1") (pinfunction "1_1") (pintype "passive"))
      (node (ref "U9") (pin "4") (pinfunction "V_LDO_4") (pintype "power_in"))
    )
    (net (code "44") (name "Net-(U10-BYP)") (class "Default")
      (node (ref "C32") (pin "1") (pinfunction "1_1") (pintype "passive"))
      (node (ref "U10") (pin "P$2") (pinfunction "BYP_P$2") (pintype "bidirectional"))
    )
    (net (code "45") (name "PULSE_SENS_GPIO") (class "Default")
      (node (ref "U8") (pin "17") (pinfunction "PA7_17") (pintype "bidirectional"))
      (node (ref "U9") (pin "13") (pinfunction "GPIO_13") (pintype "bidirectional"))
    )
    (net (code "46") (name "PULSE_SENS_IR") (class "Default")
      (node (ref "U8") (pin "16") (pinfunction "PA6_16") (pintype "bidirectional"))
      (node (ref "U9") (pin "14") (pinfunction "INTB_14") (pintype "output"))
    )
    (net (code "47") (name "SPI1_DISPLAY_CS") (class "Default")
      (node (ref "J4") (pin "17") (pinfunction "~{CS}_17") (pintype "input"))
      (node (ref "U8") (pin "32") (pinfunction "PA11_32") (pintype "bidirectional"))
    )
    (net (code "48") (name "SPI1_MOSI") (class "Default")
      (node (ref "J4") (pin "11") (pinfunction "DB1_11") (pintype "bidirectional"))
      (node (ref "U8") (pin "33") (pinfunction "PA12_33") (pintype "bidirectional"))
    )
    (net (code "49") (name "SPI1_SCLK") (class "Default")
      (node (ref "J4") (pin "12") (pinfunction "DB0_12") (pintype "input"))
      (node (ref "U8") (pin "39") (pinfunction "PB3_39") (pintype "bidirectional"))
    )
    (net (code "50") (name "SWCLK") (class "Default")
      (node (ref "J3") (pin "1") (pinfunction "SWCLK_1") (pintype "bidirectional"))
      (node (ref "U8") (pin "37") (pinfunction "PA14_37") (pintype "bidirectional"))
    )
    (net (code "51") (name "SWDIO") (class "Default")
      (node (ref "J3") (pin "4") (pinfunction "NRST_4") (pintype "bidirectional"))
      (node (ref "U8") (pin "34") (pinfunction "PA13_34") (pintype "bidirectional"))
    )
    (net (code "52") (name "USART1_RX") (class "Default")
      (node (ref "U6") (pin "10") (pinfunction "RXD_10") (pintype "input"))
      (node (ref "U8") (pin "31") (pinfunction "PA10_31") (pintype "bidirectional"))
    )
    (net (code "53") (name "USART1_TX") (class "Default")
      (node (ref "U6") (pin "7") (pinfunction "TXD_7") (pintype "output"))
      (node (ref "U8") (pin "30") (pinfunction "PA9_30") (pintype "bidirectional"))
    )
    (net (code "54") (name "VDD") (class "Default")
      (node (ref "C11") (pin "1") (pinfunction "1_1") (pintype "passive"))
      (node (ref "C23") (pin "1") (pinfunction "1_1") (pintype "passive"))
      (node (ref "C24") (pin "1") (pinfunction "1_1") (pintype "passive"))
      (node (ref "C25") (pin "1") (pinfunction "1_1") (pintype "passive"))
      (node (ref "C26") (pin "1") (pinfunction "1_1") (pintype "passive"))
      (node (ref "C27") (pin "1") (pinfunction "1_1") (pintype "passive"))
      (node (ref "C28") (pin "1") (pinfunction "1_1") (pintype "passive"))
      (node (ref "C29") (pin "1") (pinfunction "1_1") (pintype "passive"))
      (node (ref "C33") (pin "1") (pinfunction "1_1") (pintype "passive"))
      (node (ref "C38") (pin "1") (pinfunction "1_1") (pintype "passive"))
      (node (ref "C5") (pin "1") (pinfunction "1_1") (pintype "passive"))
      (node (ref "C9") (pin "1") (pinfunction "1_1") (pintype "passive"))
      (node (ref "D1") (pin "C") (pinfunction "C_C") (pintype "passive"))
      (node (ref "FB1") (pin "1") (pinfunction "P$1_1") (pintype "passive"))
      (node (ref "L1") (pin "1") (pinfunction "P$1_1") (pintype "passive"))
      (node (ref "L2") (pin "2") (pinfunction "P$2_2") (pintype "passive"))
      (node (ref "M1") (pin "2") (pinfunction "MTV_2") (pintype "bidirectional"))
      (node (ref "R10") (pin "1") (pinfunction "1_1") (pintype "passive"))
      (node (ref "R11") (pin "1") (pinfunction "1_1") (pintype "passive"))
      (node (ref "R13") (pin "1") (pinfunction "1_1") (pintype "passive"))
      (node (ref "R14") (pin "1") (pinfunction "1_1") (pintype "passive"))
      (node (ref "S1") (pin "3") (pinfunction "2_3") (pintype "bidirectional"))
      (node (ref "S1") (pin "4") (pinfunction "2'_4") (pintype "bidirectional"))
      (node (ref "S2") (pin "3") (pinfunction "2_3") (pintype "bidirectional"))
      (node (ref "S2") (pin "4") (pinfunction "2'_4") (pintype "bidirectional"))
      (node (ref "U10") (pin "P$1") (pinfunction "VDDIO_P$1") (pintype "bidirectional"))
      (node (ref "U10") (pin "P$14") (pinfunction "VDD_P$14") (pintype "bidirectional"))
      (node (ref "U11") (pin "8") (pinfunction "VCC_8") (pintype "power_in"))
      (node (ref "U2") (pin "4") (pinfunction "IN_4") (pintype "bidirectional"))
      (node (ref "U4") (pin "2") (pinfunction "VIN_2") (pintype "input"))
      (node (ref "U5") (pin "4") (pinfunction "FB_4") (pintype "input"))
      (node (ref "U8") (pin "24") (pinfunction "VDD_1_24") (pintype "power_in"))
      (node (ref "U8") (pin "36") (pinfunction "VDD_2_36") (pintype "power_in"))
      (node (ref "U8") (pin "48") (pinfunction "VDD_3_48") (pintype "power_in"))
      (node (ref "U9") (pin "5") (pinfunction "V_LED_5") (pintype "power_in"))
    )
    (net (code "55") (name "VDD_RAW") (class "Default")
      (node (ref "C10") (pin "1") (pinfunction "1_1") (pintype "passive"))
      (node (ref "C7") (pin "1") (pinfunction "1_1") (pintype "passive"))
      (node (ref "U3") (pin "1") (pinfunction "VOUT_1") (pintype "output"))
      (node (ref "U5") (pin "1") (pinfunction "V1_1") (pintype "power_in"))
      (node (ref "U5") (pin "3") (pinfunction "EN_3") (pintype "input"))
    )
    (net (code "56") (name "V_BAT") (class "Default")
      (node (ref "C3") (pin "1") (pinfunction "1_1") (pintype "passive"))
      (node (ref "J2") (pin "1") (pinfunction "VBAT+_1") (pintype "power_in"))
      (node (ref "U1") (pin "3") (pinfunction "VBAT_3") (pintype "bidirectional"))
      (node (ref "U3") (pin "8") (pinfunction "VBAT_8") (pintype "passive"))
    )
    (net (code "57") (name "unconnected-(J1-ID-Pad4)") (class "Default")
      (node (ref "J1") (pin "4") (pinfunction "ID_4") (pintype "no_connect"))
    )
    (net (code "58") (name "unconnected-(J4-DB2-Pad10)") (class "Default")
      (node (ref "J4") (pin "10") (pinfunction "DB2_10") (pintype "bidirectional"))
    )
    (net (code "59") (name "unconnected-(U2-NC-Pad6)") (class "Default")
      (node (ref "U2") (pin "6") (pinfunction "NC_6") (pintype "no_connect"))
    )
    (net (code "60") (name "unconnected-(U3-~{RST}-Pad7)") (class "Default")
      (node (ref "U3") (pin "7") (pinfunction "~{RST}_7") (pintype "passive"))
    )
    (net (code "61") (name "unconnected-(U4-NC-Pad5)") (class "Default")
      (node (ref "U4") (pin "5") (pinfunction "NC_5") (pintype "no_connect"))
    )
    (net (code "62") (name "unconnected-(U6-CBUS0-Pad6)") (class "Default")
      (node (ref "U6") (pin "6") (pinfunction "CBUS0_6") (pintype "bidirectional"))
    )
    (net (code "63") (name "unconnected-(U6-{slash}CTS-Pad11)") (class "Default")
      (node (ref "U6") (pin "11") (pinfunction "/CTS_11") (pintype "input"))
    )
    (net (code "64") (name "unconnected-(U6-{slash}RTS-Pad8)") (class "Default")
      (node (ref "U6") (pin "8") (pinfunction "/RTS_8") (pintype "output"))
    )
    (net (code "65") (name "unconnected-(U8A-OSC_IN-Pad5)") (class "Default")
      (node (ref "U8") (pin "5") (pinfunction "OSC_IN_5") (pintype "bidirectional"))
    )
    (net (code "66") (name "unconnected-(U8A-OSC_OUT-Pad6)") (class "Default")
      (node (ref "U8") (pin "6") (pinfunction "OSC_OUT_6") (pintype "bidirectional"))
    )
    (net (code "67") (name "unconnected-(U8B-PA15-Pad38)") (class "Default")
      (node (ref "U8") (pin "38") (pinfunction "PA15_38") (pintype "bidirectional"))
    )
    (net (code "68") (name "unconnected-(U8C-PB2-Pad20)") (class "Default")
      (node (ref "U8") (pin "20") (pinfunction "PB2_20") (pintype "bidirectional"))
    )
    (net (code "69") (name "unconnected-(U8C-PB4-Pad40)") (class "Default")
      (node (ref "U8") (pin "40") (pinfunction "PB4_40") (pintype "bidirectional"))
    )
    (net (code "70") (name "unconnected-(U8C-PB5-Pad41)") (class "Default")
      (node (ref "U8") (pin "41") (pinfunction "PB5_41") (pintype "bidirectional"))
    )
    (net (code "71") (name "unconnected-(U8C-PB6-Pad42)") (class "Default")
      (node (ref "U8") (pin "42") (pinfunction "PB6_42") (pintype "bidirectional"))
    )
    (net (code "72") (name "unconnected-(U8C-PB7-Pad43)") (class "Default")
      (node (ref "U8") (pin "43") (pinfunction "PB7_43") (pintype "bidirectional"))
    )
    (net (code "73") (name "unconnected-(U8C-PB8-Pad45)") (class "Default")
      (node (ref "U8") (pin "45") (pinfunction "PB8_45") (pintype "bidirectional"))
    )
    (net (code "74") (name "unconnected-(U8C-PB9-Pad46)") (class "Default")
      (node (ref "U8") (pin "46") (pinfunction "PB9_46") (pintype "bidirectional"))
    )
    (net (code "75") (name "unconnected-(U10-NC1-PadP$3)") (class "Default")
      (node (ref "U10") (pin "P$3") (pinfunction "NC1_P$3") (pintype "bidirectional"))
    )
    (net (code "76") (name "unconnected-(U10-NC2-PadP$8)") (class "Default")
      (node (ref "U10") (pin "P$8") (pinfunction "NC2_P$8") (pintype "bidirectional"))
    )
    (net (code "77") (name "unconnected-(U10-NC3-PadP$13)") (class "Default")
      (node (ref "U10") (pin "P$13") (pinfunction "NC3_P$13") (pintype "bidirectional"))
    )
    (net (code "78") (name "unconnected-(U10-NC4-PadP$15)") (class "Default")
      (node (ref "U10") (pin "P$15") (pinfunction "NC4_P$15") (pintype "bidirectional"))
    )
    (net (code "79") (name "unconnected-(U10-NC5-PadP$16)") (class "Default")
      (node (ref "U10") (pin "P$16") (pinfunction "NC5_P$16") (pintype "bidirectional"))
    )
    (net (code "80") (name "unconnected-(U11-A0-Pad1)") (class "Default")
      (node (ref "U11") (pin "1") (pinfunction "A0_1") (pintype "tri_state"))
    )
  )
)
